# I2C_Expantion_sch.net
KiCad netlist of a schematic drawn in EAGLE
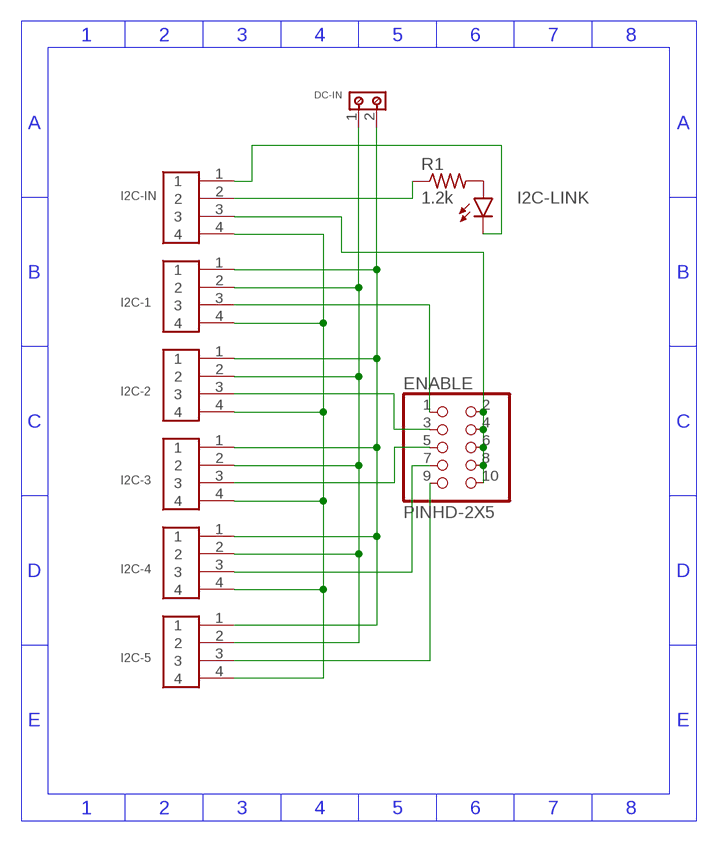
[diagram p0: schematic, sheet 1]

(export (version "E")
  (design (tool "Eeschema 10.0.6"))
  (components
    (comp (ref "DC-IN")
      (value "691201620002")
      (footprint "eagle-import:691201620002")
      (libsource (lib "eagle-import") (part "691201620002"))
    )
    (comp (ref "ENABLE")
      (value "PINHD-2X5")
      (footprint "eagle-import:2X05")
      (libsource (lib "eagle-import") (part "PINHD-2X5"))
    )
    (comp (ref "I2C-1")
      (value "B4B-XH-A(LF)(SN)")
      (footprint "eagle-import:B4B-XH-A(LF)(SN)")
      (fields
        (field (name "DIGIKEY_PARTNO") "455-2249-ND")
        (field (name "MANUFACTURER") "JST Sales America Inc.")
        (field (name "CREATED_BY") "PCBLayout.com")
      )
      (libsource (lib "eagle-import") (part "B4B-XH-A(LF)(SN)"))
    )
    (comp (ref "I2C-2")
      (value "B4B-XH-A(LF)(SN)")
      (footprint "eagle-import:B4B-XH-A(LF)(SN)")
      (fields
        (field (name "DIGIKEY_PARTNO") "455-2249-ND")
        (field (name "MANUFACTURER") "JST Sales America Inc.")
        (field (name "CREATED_BY") "PCBLayout.com")
      )
      (libsource (lib "eagle-import") (part "B4B-XH-A(LF)(SN)"))
    )
    (comp (ref "I2C-3")
      (value "B4B-XH-A(LF)(SN)")
      (footprint "eagle-import:B4B-XH-A(LF)(SN)")
      (fields
        (field (name "DIGIKEY_PARTNO") "455-2249-ND")
        (field (name "MANUFACTURER") "JST Sales America Inc.")
        (field (name "CREATED_BY") "PCBLayout.com")
      )
      (libsource (lib "eagle-import") (part "B4B-XH-A(LF)(SN)"))
    )
    (comp (ref "I2C-4")
      (value "B4B-XH-A(LF)(SN)")
      (footprint "eagle-import:B4B-XH-A(LF)(SN)")
      (fields
        (field (name "DIGIKEY_PARTNO") "455-2249-ND")
        (field (name "MANUFACTURER") "JST Sales America Inc.")
        (field (name "CREATED_BY") "PCBLayout.com")
      )
      (libsource (lib "eagle-import") (part "B4B-XH-A(LF)(SN)"))
    )
    (comp (ref "I2C-5")
      (value "B4B-XH-A(LF)(SN)")
      (footprint "eagle-import:B4B-XH-A(LF)(SN)")
      (fields
        (field (name "DIGIKEY_PARTNO") "455-2249-ND")
        (field (name "MANUFACTURER") "JST Sales America Inc.")
        (field (name "CREATED_BY") "PCBLayout.com")
      )
      (libsource (lib "eagle-import") (part "B4B-XH-A(LF)(SN)"))
    )
    (comp (ref "I2C-IN")
      (value "B4B-XH-A(LF)(SN)")
      (footprint "eagle-import:B4B-XH-A(LF)(SN)")
      (fields
        (field (name "DIGIKEY_PARTNO") "455-2249-ND")
        (field (name "MANUFACTURER") "JST Sales America Inc.")
        (field (name "CREATED_BY") "PCBLayout.com")
      )
      (libsource (lib "eagle-import") (part "B4B-XH-A(LF)(SN)"))
    )
    (comp (ref "I2C-LINK")
      (value "LED_BLUE")
      (footprint "eagle-import:LEDRD254W60D565H860B_B")
      (libsource (lib "eagle-import") (part "LED_RADIALBLUE_"))
    )
    (comp (ref "R1")
      (value "1.2k")
      (footprint "eagle-import:RESAD724W46L381D178B")
      (libsource (lib "eagle-import") (part "R-USAXIAL-7.2MM-PITCH_"))
    )
  )
  (nets
    (net (code "1") (name "Net-(DC-IN-Pad1)") (class "Default")
      (node (ref "DC-IN") (pin "1") (pinfunction "1_1") (pintype "passive"))
      (node (ref "I2C-1") (pin "2") (pinfunction "2_2") (pintype "passive"))
      (node (ref "I2C-2") (pin "2") (pinfunction "2_2") (pintype "passive"))
      (node (ref "I2C-3") (pin "2") (pinfunction "2_2") (pintype "passive"))
      (node (ref "I2C-4") (pin "2") (pinfunction "2_2") (pintype "passive"))
      (node (ref "I2C-5") (pin "2") (pinfunction "2_2") (pintype "passive"))
    )
    (net (code "2") (name "Net-(DC-IN-Pad2)") (class "Default")
      (node (ref "DC-IN") (pin "2") (pinfunction "2_2") (pintype "passive"))
      (node (ref "I2C-1") (pin "1") (pinfunction "1_1") (pintype "passive"))
      (node (ref "I2C-2") (pin "1") (pinfunction "1_1") (pintype "passive"))
      (node (ref "I2C-3") (pin "1") (pinfunction "1_1") (pintype "passive"))
      (node (ref "I2C-4") (pin "1") (pinfunction "1_1") (pintype "passive"))
      (node (ref "I2C-5") (pin "1") (pinfunction "1_1") (pintype "passive"))
    )
    (net (code "3") (name "Net-(ENABLE-Pad1)") (class "Default")
      (node (ref "ENABLE") (pin "1") (pinfunction "1_1") (pintype "passive"))
      (node (ref "I2C-1") (pin "3") (pinfunction "3_3") (pintype "passive"))
    )
    (net (code "4") (name "Net-(ENABLE-Pad3)") (class "Default")
      (node (ref "ENABLE") (pin "3") (pinfunction "3_3") (pintype "passive"))
      (node (ref "I2C-2") (pin "3") (pinfunction "3_3") (pintype "passive"))
    )
    (net (code "5") (name "Net-(ENABLE-Pad5)") (class "Default")
      (node (ref "ENABLE") (pin "5") (pinfunction "5_5") (pintype "passive"))
      (node (ref "I2C-3") (pin "3") (pinfunction "3_3") (pintype "passive"))
    )
    (net (code "6") (name "Net-(ENABLE-Pad7)") (class "Default")
      (node (ref "ENABLE") (pin "7") (pinfunction "7_7") (pintype "passive"))
      (node (ref "I2C-4") (pin "3") (pinfunction "3_3") (pintype "passive"))
    )
    (net (code "7") (name "Net-(ENABLE-Pad9)") (class "Default")
      (node (ref "ENABLE") (pin "9") (pinfunction "9_9") (pintype "passive"))
      (node (ref "I2C-5") (pin "3") (pinfunction "3_3") (pintype "passive"))
    )
    (net (code "8") (name "Net-(ENABLE-Pad10)") (class "Default")
      (node (ref "ENABLE") (pin "10") (pinfunction "10_10") (pintype "passive"))
      (node (ref "ENABLE") (pin "2") (pinfunction "2_2") (pintype "passive"))
      (node (ref "ENABLE") (pin "4") (pinfunction "4_4") (pintype "passive"))
      (node (ref "ENABLE") (pin "6") (pinfunction "6_6") (pintype "passive"))
      (node (ref "ENABLE") (pin "8") (pinfunction "8_8") (pintype "passive"))
      (node (ref "I2C-IN") (pin "3") (pinfunction "3_3") (pintype "passive"))
    )
    (net (code "9") (name "Net-(I2C-1-Pad4)") (class "Default")
      (node (ref "I2C-1") (pin "4") (pinfunction "4_4") (pintype "passive"))
      (node (ref "I2C-2") (pin "4") (pinfunction "4_4") (pintype "passive"))
      (node (ref "I2C-3") (pin "4") (pinfunction "4_4") (pintype "passive"))
      (node (ref "I2C-4") (pin "4") (pinfunction "4_4") (pintype "passive"))
      (node (ref "I2C-5") (pin "4") (pinfunction "4_4") (pintype "passive"))
      (node (ref "I2C-IN") (pin "4") (pinfunction "4_4") (pintype "passive"))
    )
    (net (code "10") (name "Net-(I2C-IN-Pad2)") (class "Default")
      (node (ref "I2C-IN") (pin "2") (pinfunction "2_2") (pintype "passive"))
      (node (ref "R1") (pin "1") (pinfunction "1_1") (pintype "passive"))
    )
    (net (code "11") (name "Net-(I2C-LINK-A)") (class "Default")
      (node (ref "I2C-LINK") (pin "1") (pinfunction "A_1") (pintype "passive"))
      (node (ref "R1") (pin "2") (pinfunction "2_2") (pintype "passive"))
    )
    (net (code "12") (name "Net-(I2C-LINK-C)") (class "Default")
      (node (ref "I2C-IN") (pin "1") (pinfunction "1_1") (pintype "passive"))
      (node (ref "I2C-LINK") (pin "2") (pinfunction "C_2") (pintype "passive"))
    )
  )
)
